# Sch_mcu.net
KiCad netlist of a schematic drawn in Altium Designer
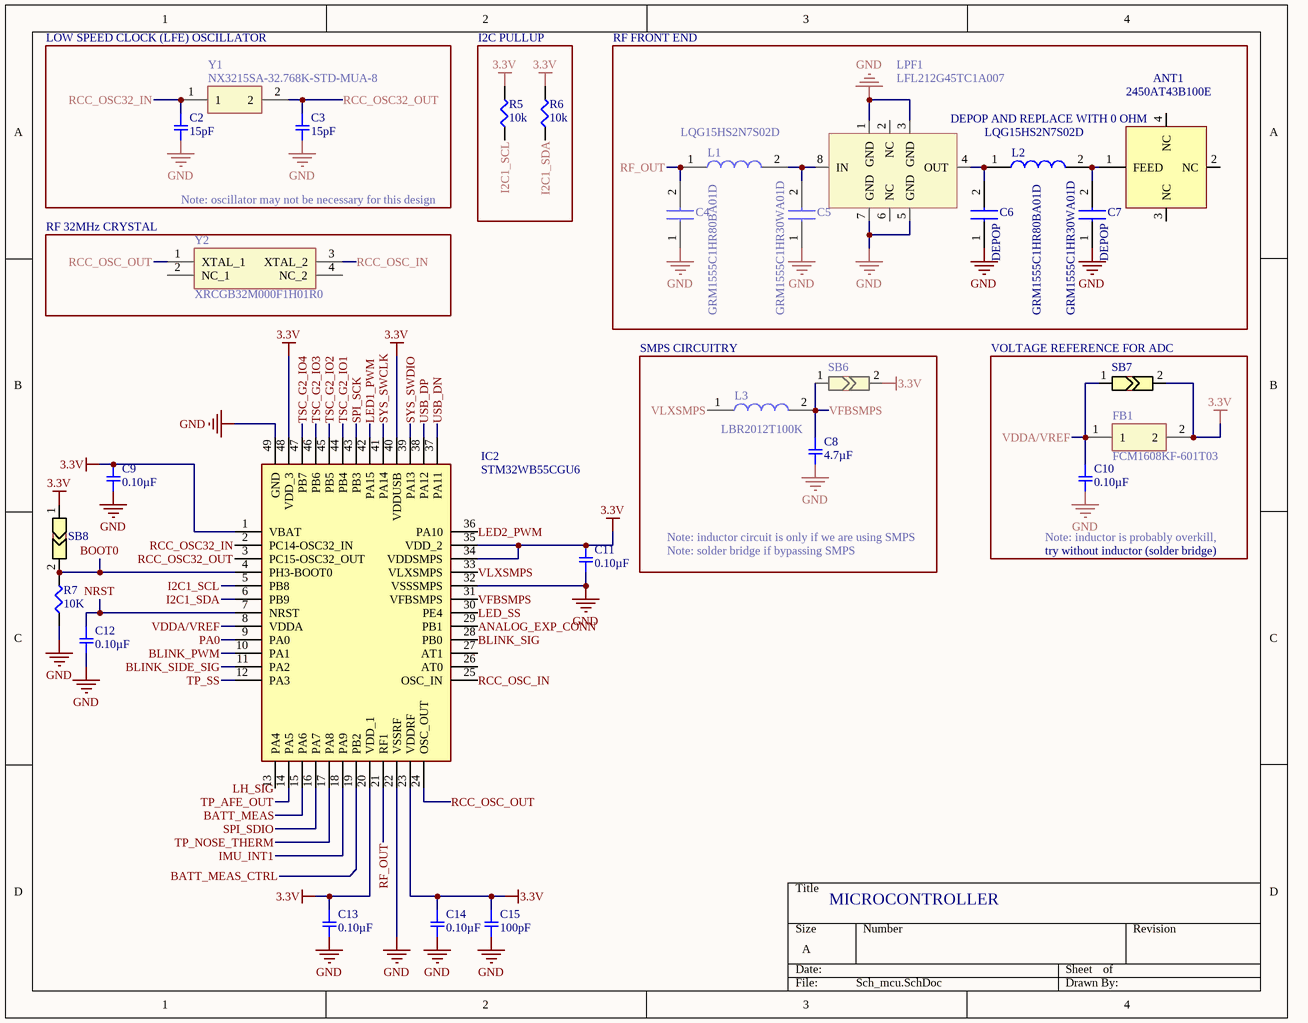
[diagram p0: Sch_mcu.SchDoc]

(export (version "E")
  (design (tool "Eeschema 10.0.6"))
  (components
    (comp (ref "ANT1")
      (value "2450AT43B100E")
      (footprint "2450AT43B100E")
      (libsource (lib "schematic_components") (part "2450AT43B100E"))
    )
    (comp (ref "C2")
      (value "15pF")
      (footprint "SMD-0402C")
      (description "CAP CER 15PF 50V NP0 0402")
      (fields
        (field (name "DIGI-KEY PART NUMBER") "490-11147-1-ND")
        (field (name "PART NUMBER") "GCM1555C1H150JA16D")
      )
      (libsource (lib "capacitor_murata_0402") (part "GCM1555C1H150JA16D"))
    )
    (comp (ref "C3")
      (value "15pF")
      (footprint "SMD-0402C")
      (description "CAP CER 15PF 50V NP0 0402")
      (fields
        (field (name "DIGI-KEY PART NUMBER") "490-11147-1-ND")
        (field (name "PART NUMBER") "GCM1555C1H150JA16D")
      )
      (libsource (lib "capacitor_murata_0402") (part "GCM1555C1H150JA16D"))
    )
    (comp (ref "C4")
      (value "GRM1555C1HR80BA01D")
      (footprint "SamacSys:CAPC1005X55N")
      (description "Capacitor")
      (fields
        (field (name "MOUSER PART NUMBER") "81-GRM1555C1HR80BA1D")
        (field (name "RS PART NUMBER") "8145426P")
      )
      (libsource (lib "*") (part "GRM1555C1HR80BA01D"))
    )
    (comp (ref "C5")
      (value "GRM1555C1HR30WA01D")
      (footprint "SamacSys:CAPC1005X55N")
      (description "Capacitor")
      (fields
        (field (name "MOUSER PART NUMBER") "81-GRM1555C1HR30WA1D")
        (field (name "RS PART NUMBER") "8145394P")
      )
      (libsource (lib "*") (part "GRM1555C1HR30WA01D"))
    )
    (comp (ref "C6")
      (value "GRM1555C1HR80BA01D")
      (footprint "SamacSys:CAPC1005X55N")
      (description "Capacitor")
      (fields
        (field (name "MOUSER PART NUMBER") "81-GRM1555C1HR80BA1D")
        (field (name "RS PART NUMBER") "8145426P")
      )
      (libsource (lib "*") (part "GRM1555C1HR80BA01D"))
    )
    (comp (ref "C7")
      (value "GRM1555C1HR30WA01D")
      (footprint "SamacSys:CAPC1005X55N")
      (description "Capacitor")
      (fields
        (field (name "MOUSER PART NUMBER") "81-GRM1555C1HR30WA1D")
        (field (name "RS PART NUMBER") "8145394P")
      )
      (libsource (lib "*") (part "GRM1555C1HR30WA01D"))
    )
    (comp (ref "C8")
      (value "4.7µF")
      (footprint "SMD-0402C")
      (description "CAP CER 4.7UF 4V X5R 0402")
      (fields
        (field (name "DIGI-KEY PART NUMBER") "490-13231-1-ND")
        (field (name "PART NUMBER") "GRM153R60G475ME15D")
      )
      (libsource (lib "capacitor_murata_0402") (part "GRM153R60G475ME15D"))
    )
    (comp (ref "C9")
      (value "0.10µF")
      (footprint "SMD-0402C")
      (description "CAP CER 0.1UF 16V X7R 0402")
      (fields
        (field (name "DIGI-KEY PART NUMBER") "490-4759-1-ND")
        (field (name "PART NUMBER") "GCM155R71C104KA55D")
      )
      (libsource (lib "capacitor_murata_0402") (part "GCM155R71C104KA55D"))
    )
    (comp (ref "C10")
      (value "0.10µF")
      (footprint "SMD-0402C")
      (description "CAP CER 0.1UF 16V X7R 0402")
      (fields
        (field (name "DIGI-KEY PART NUMBER") "490-4759-1-ND")
        (field (name "PART NUMBER") "GCM155R71C104KA55D")
      )
      (libsource (lib "capacitor_murata_0402") (part "GCM155R71C104KA55D"))
    )
    (comp (ref "C11")
      (value "0.10µF")
      (footprint "SMD-0402C")
      (description "CAP CER 0.1UF 16V X7R 0402")
      (fields
        (field (name "DIGI-KEY PART NUMBER") "490-4759-1-ND")
        (field (name "PART NUMBER") "GCM155R71C104KA55D")
      )
      (libsource (lib "capacitor_murata_0402") (part "GCM155R71C104KA55D"))
    )
    (comp (ref "C12")
      (value "0.10µF")
      (footprint "SMD-0402C")
      (description "CAP CER 0.1UF 16V X7R 0402")
      (fields
        (field (name "DIGI-KEY PART NUMBER") "490-4759-1-ND")
        (field (name "PART NUMBER") "GCM155R71C104KA55D")
      )
      (libsource (lib "capacitor_murata_0402") (part "GCM155R71C104KA55D"))
    )
    (comp (ref "C13")
      (value "0.10µF")
      (footprint "SMD-0402C")
      (description "CAP CER 0.1UF 16V X7R 0402")
      (fields
        (field (name "DIGI-KEY PART NUMBER") "490-4759-1-ND")
        (field (name "PART NUMBER") "GCM155R71C104KA55D")
      )
      (libsource (lib "capacitor_murata_0402") (part "GCM155R71C104KA55D"))
    )
    (comp (ref "C14")
      (value "0.10µF")
      (footprint "SMD-0402C")
      (description "CAP CER 0.1UF 16V X7R 0402")
      (fields
        (field (name "DIGI-KEY PART NUMBER") "490-4759-1-ND")
        (field (name "PART NUMBER") "GCM155R71C104KA55D")
      )
      (libsource (lib "capacitor_murata_0402") (part "GCM155R71C104KA55D"))
    )
    (comp (ref "C15")
      (value "100pF")
      (footprint "SMD-0402C")
      (description "CAP CER 100PF 50V NP0 0402")
      (fields
        (field (name "DIGI-KEY PART NUMBER") "490-10669-1-ND")
        (field (name "PART NUMBER") "GCM1555C1H101JA16D")
      )
      (libsource (lib "capacitor_murata_0402") (part "GCM1555C1H101JA16D"))
    )
    (comp (ref "FB1")
      (value "FCM1608KF-601T03")
      (footprint "SamacSys:BEADC1608X95N")
      (description "Ferrite Bead")
      (libsource (lib "*") (part "FCM1608KF-601T03"))
    )
    (comp (ref "IC2")
      (value "STM32WB55CGU6")
      (footprint "SamacSys:QFN50P700X700X65-49N-D")
      (description "Integrated Circuit")
      (fields (field (name "MOUSER PART NUMBER") "511-STM32WB55CGU6"))
      (libsource (lib "*") (part "STM32WB55CGU6"))
    )
    (comp (ref "L1")
      (value "LQG15HS2N7S02D")
      (footprint "SamacSys:INDC1005X55N")
      (description "Inductor")
      (libsource (lib "*") (part "LQG15HS2N7S02D"))
    )
    (comp (ref "L2")
      (value "LQG15HS2N7S02D")
      (footprint "SamacSys:INDC1005X55N")
      (description "Inductor")
      (libsource (lib "*") (part "LQG15HS2N7S02D"))
    )
    (comp (ref "L3")
      (value "LBR2012T100K")
      (footprint "SamacSys:INDC2012X145N")
      (description "Inductor")
      (fields (field (name "MOUSER PART NUMBER") "963-LBR2012T100K"))
      (libsource (lib "*") (part "LBR2012T100K"))
    )
    (comp (ref "LPF1")
      (value "LFL212G45TC1A007")
      (footprint "custom_footprints:LFL212G45TC1A007")
      (libsource (lib "SamacSys") (part "LFL212G45TC1A007"))
    )
    (comp (ref "R5")
      (value "10k")
      (footprint "SMD-0402-RES")
      (description "RES SMD 10K OHM 5% 1/10W 0402")
      (fields (field (name "PART NUMBER") "ERJ-2GEJ103X") (field (name "DIGI-KEY PART NUMBER") "P10KJCT-ND"))
      (libsource (lib "Panasonic_ERJ_0402") (part "ERJ-2GEJ103X"))
    )
    (comp (ref "R6")
      (value "10k")
      (footprint "SMD-0402-RES")
      (description "RES SMD 10K OHM 5% 1/10W 0402")
      (fields (field (name "PART NUMBER") "ERJ-2GEJ103X") (field (name "DIGI-KEY PART NUMBER") "P10KJCT-ND"))
      (libsource (lib "Panasonic_ERJ_0402") (part "ERJ-2GEJ103X"))
    )
    (comp (ref "R7")
      (value "10K")
      (footprint "SMD-0402-RES")
      (description "RES SMD 10K OHM 1% 1/10W 0402")
      (fields
        (field (name "PART NUMBER") "ERJ-2RKF1003X")
        (field (name "DIGI-KEY PART NUMBER") "P100KLCT-ND")
      )
      (libsource (lib "Panasonic_ERJ_0402") (part "ERJ-2RKF1003X"))
    )
    (comp (ref "SB6")
      (value "SOLDER_JUMPER")
      (footprint "custom_footprints:JUMPER_SMD")
      (libsource (lib "SamacSys") (part "SOLDER_JUMPER"))
    )
    (comp (ref "SB7")
      (value "SOLDER_JUMPER")
      (footprint "custom_footprints:JUMPER_SMD")
      (libsource (lib "SamacSys") (part "SOLDER_JUMPER"))
    )
    (comp (ref "SB8")
      (value "SOLDER_JUMPER")
      (footprint "custom_footprints:JUMPER_SMD")
      (libsource (lib "") (part "SOLDER_JUMPER_1"))
    )
    (comp (ref "Y1")
      (value "NX3215SA-32.768K-STD-MUA-8")
      (footprint "SamacSys:NX3215SA")
      (description "Crystal or Oscillator")
      (fields (field (name "MOUSER PART NUMBER") "344-NX3215SA32768K8"))
      (libsource (lib "*") (part "NX3215SA-32.768K-STD-MUA-8"))
    )
    (comp (ref "Y2")
      (value "XRCGB32M000F1H01R0")
      (footprint "SamacSys:XRCGB32M000F1H01R0")
      (description "Crystal or Oscillator")
      (fields (field (name "MOUSER PART NUMBER") "81-XRCGB32M000F1H01R"))
      (libsource (lib "*") (part "XRCGB32M000F1H01R0"))
    )
  )
  (nets
    (net (code "1") (name "/ANALOG_EXP_CONN") (class "Default")
      (node (ref "IC2") (pin "29") (pinfunction "PB1_29") (pintype "passive"))
    )
    (net (code "2") (name "/BATT_MEAS") (class "Default")
      (node (ref "IC2") (pin "15") (pinfunction "PA6_15") (pintype "passive"))
    )
    (net (code "3") (name "/BATT_MEAS_CTRL") (class "Default")
      (node (ref "IC2") (pin "19") (pinfunction "PB2_19") (pintype "passive"))
    )
    (net (code "4") (name "/BLINK_PWM") (class "Default")
      (node (ref "IC2") (pin "10") (pinfunction "PA1_10") (pintype "passive"))
    )
    (net (code "5") (name "/BLINK_SIDE_SIG") (class "Default")
      (node (ref "IC2") (pin "11") (pinfunction "PA2_11") (pintype "passive"))
    )
    (net (code "6") (name "/BLINK_SIG") (class "Default")
      (node (ref "IC2") (pin "28") (pinfunction "PB0_28") (pintype "passive"))
    )
    (net (code "7") (name "/BOOT0") (class "Default")
      (node (ref "IC2") (pin "4") (pinfunction "PH3-BOOT0_4") (pintype "passive"))
      (node (ref "R7") (pin "2") (pinfunction "2_2") (pintype "passive"))
      (node (ref "SB8") (pin "2") (pinfunction "1_2") (pintype "passive"))
    )
    (net (code "8") (name "/I2C1_SCL") (class "Default")
      (node (ref "IC2") (pin "5") (pinfunction "PB8_5") (pintype "passive"))
      (node (ref "R5") (pin "1") (pinfunction "1_1") (pintype "passive"))
    )
    (net (code "9") (name "/I2C1_SDA") (class "Default")
      (node (ref "IC2") (pin "6") (pinfunction "PB9_6") (pintype "passive"))
      (node (ref "R6") (pin "1") (pinfunction "1_1") (pintype "passive"))
    )
    (net (code "10") (name "/IMU_INT1") (class "Default")
      (node (ref "IC2") (pin "18") (pinfunction "PA9_18") (pintype "passive"))
    )
    (net (code "11") (name "/LED1_PWM") (class "Default")
      (node (ref "IC2") (pin "42") (pinfunction "PA15_42") (pintype "passive"))
    )
    (net (code "12") (name "/LED2_PWM") (class "Default")
      (node (ref "IC2") (pin "36") (pinfunction "PA10_36") (pintype "passive"))
    )
    (net (code "13") (name "/LED_SS") (class "Default")
      (node (ref "IC2") (pin "30") (pinfunction "PE4_30") (pintype "passive"))
    )
    (net (code "14") (name "/LH_SIG") (class "Default")
      (node (ref "IC2") (pin "13") (pinfunction "PA4_13") (pintype "passive"))
    )
    (net (code "15") (name "/NRST") (class "Default")
      (node (ref "C12") (pin "1") (pinfunction "1_1") (pintype "passive"))
      (node (ref "IC2") (pin "7") (pinfunction "NRST_7") (pintype "passive"))
    )
    (net (code "16") (name "/PA0") (class "Default")
      (node (ref "IC2") (pin "9") (pinfunction "PA0_9") (pintype "passive"))
    )
    (net (code "17") (name "/RCC_OSC32_IN") (class "Default")
      (node (ref "C2") (pin "1") (pinfunction "1_1") (pintype "passive"))
      (node (ref "IC2") (pin "2") (pinfunction "PC14-OSC32_IN_2") (pintype "passive"))
      (node (ref "Y1") (pin "1") (pinfunction "1_1") (pintype "passive"))
    )
    (net (code "18") (name "/RCC_OSC32_OUT") (class "Default")
      (node (ref "C3") (pin "1") (pinfunction "1_1") (pintype "passive"))
      (node (ref "IC2") (pin "3") (pinfunction "PC15-OSC32_OUT_3") (pintype "passive"))
      (node (ref "Y1") (pin "2") (pinfunction "2_2") (pintype "passive"))
    )
    (net (code "19") (name "/RCC_OSC_IN") (class "Default")
      (node (ref "IC2") (pin "25") (pinfunction "OSC_IN_25") (pintype "passive"))
      (node (ref "Y2") (pin "3") (pinfunction "XTAL_2_3") (pintype "passive"))
    )
    (net (code "20") (name "/RCC_OSC_OUT") (class "Default")
      (node (ref "IC2") (pin "24") (pinfunction "OSC_OUT_24") (pintype "passive"))
      (node (ref "Y2") (pin "1") (pinfunction "XTAL_1_1") (pintype "passive"))
    )
    (net (code "21") (name "/RF_OUT") (class "Default")
      (node (ref "C4") (pin "2") (pinfunction "2_2") (pintype "passive"))
      (node (ref "IC2") (pin "21") (pinfunction "RF1_21") (pintype "passive"))
      (node (ref "L1") (pin "1") (pinfunction "1_1") (pintype "passive"))
    )
    (net (code "22") (name "/SPI_SCK") (class "Default")
      (node (ref "IC2") (pin "43") (pinfunction "PB3_43") (pintype "passive"))
    )
    (net (code "23") (name "/SPI_SDIO") (class "Default")
      (node (ref "IC2") (pin "16") (pinfunction "PA7_16") (pintype "passive"))
    )
    (net (code "24") (name "/SYS_SWCLK") (class "Default")
      (node (ref "IC2") (pin "41") (pinfunction "PA14_41") (pintype "passive"))
    )
    (net (code "25") (name "/SYS_SWDIO") (class "Default")
      (node (ref "IC2") (pin "39") (pinfunction "PA13_39") (pintype "passive"))
    )
    (net (code "26") (name "/TP_AFE_OUT") (class "Default")
      (node (ref "IC2") (pin "14") (pinfunction "PA5_14") (pintype "passive"))
    )
    (net (code "27") (name "/TP_NOSE_THERM") (class "Default")
      (node (ref "IC2") (pin "17") (pinfunction "PA8_17") (pintype "passive"))
    )
    (net (code "28") (name "/TP_SS") (class "Default")
      (node (ref "IC2") (pin "12") (pinfunction "PA3_12") (pintype "passive"))
    )
    (net (code "29") (name "/TSC_G2_IO1") (class "Default")
      (node (ref "IC2") (pin "44") (pinfunction "PB4_44") (pintype "passive"))
    )
    (net (code "30") (name "/TSC_G2_IO2") (class "Default")
      (node (ref "IC2") (pin "45") (pinfunction "PB5_45") (pintype "passive"))
    )
    (net (code "31") (name "/TSC_G2_IO3") (class "Default")
      (node (ref "IC2") (pin "46") (pinfunction "PB6_46") (pintype "passive"))
    )
    (net (code "32") (name "/TSC_G2_IO4") (class "Default")
      (node (ref "IC2") (pin "47") (pinfunction "PB7_47") (pintype "passive"))
    )
    (net (code "33") (name "/USB_DN") (class "Default")
      (node (ref "IC2") (pin "37") (pinfunction "PA11_37") (pintype "passive"))
    )
    (net (code "34") (name "/USB_DP") (class "Default")
      (node (ref "IC2") (pin "38") (pinfunction "PA12_38") (pintype "passive"))
    )
    (net (code "35") (name "/VDDA{slash}VREF") (class "Default")
      (node (ref "C10") (pin "1") (pinfunction "1_1") (pintype "passive"))
      (node (ref "FB1") (pin "1") (pinfunction "1_1") (pintype "passive"))
      (node (ref "IC2") (pin "8") (pinfunction "VDDA_8") (pintype "passive"))
      (node (ref "SB7") (pin "1") (pinfunction "1_1") (pintype "passive"))
    )
    (net (code "36") (name "/VFBSMPS") (class "Default")
      (node (ref "C8") (pin "1") (pinfunction "1_1") (pintype "passive"))
      (node (ref "IC2") (pin "31") (pinfunction "VFBSMPS_31") (pintype "passive"))
      (node (ref "L3") (pin "2") (pinfunction "2_2") (pintype "passive"))
      (node (ref "SB6") (pin "1") (pinfunction "1_1") (pintype "passive"))
    )
    (net (code "37") (name "/VLXSMPS") (class "Default")
      (node (ref "IC2") (pin "33") (pinfunction "VLXSMPS_33") (pintype "passive"))
      (node (ref "L3") (pin "1") (pinfunction "1_1") (pintype "passive"))
    )
    (net (code "38") (name "3.3V") (class "Default")
      (node (ref "C11") (pin "1") (pinfunction "1_1") (pintype "passive"))
      (node (ref "C13") (pin "1") (pinfunction "1_1") (pintype "passive"))
      (node (ref "C14") (pin "1") (pinfunction "1_1") (pintype "passive"))
      (node (ref "C15") (pin "1") (pinfunction "1_1") (pintype "passive"))
      (node (ref "C9") (pin "1") (pinfunction "1_1") (pintype "passive"))
      (node (ref "FB1") (pin "2") (pinfunction "2_2") (pintype "passive"))
      (node (ref "IC2") (pin "1") (pinfunction "VBAT_1") (pintype "passive"))
      (node (ref "IC2") (pin "20") (pinfunction "VDD_1_20") (pintype "passive"))
      (node (ref "IC2") (pin "23") (pinfunction "VDDRF_23") (pintype "passive"))
      (node (ref "IC2") (pin "34") (pinfunction "VDDSMPS_34") (pintype "passive"))
      (node (ref "IC2") (pin "35") (pinfunction "VDD_2_35") (pintype "passive"))
      (node (ref "IC2") (pin "40") (pinfunction "VDDUSB_40") (pintype "passive"))
      (node (ref "IC2") (pin "48") (pinfunction "VDD_3_48") (pintype "passive"))
      (node (ref "R5") (pin "2") (pinfunction "2_2") (pintype "passive"))
      (node (ref "R6") (pin "2") (pinfunction "2_2") (pintype "passive"))
      (node (ref "SB6") (pin "2") (pinfunction "1_2") (pintype "passive"))
      (node (ref "SB7") (pin "2") (pinfunction "1_2") (pintype "passive"))
      (node (ref "SB8") (pin "1") (pinfunction "1_1") (pintype "passive"))
    )
    (net (code "39") (name "GND") (class "Default")
      (node (ref "C10") (pin "2") (pinfunction "2_2") (pintype "passive"))
      (node (ref "C11") (pin "2") (pinfunction "2_2") (pintype "passive"))
      (node (ref "C12") (pin "2") (pinfunction "2_2") (pintype "passive"))
      (node (ref "C13") (pin "2") (pinfunction "2_2") (pintype "passive"))
      (node (ref "C14") (pin "2") (pinfunction "2_2") (pintype "passive"))
      (node (ref "C15") (pin "2") (pinfunction "2_2") (pintype "passive"))
      (node (ref "C2") (pin "2") (pinfunction "2_2") (pintype "passive"))
      (node (ref "C3") (pin "2") (pinfunction "2_2") (pintype "passive"))
      (node (ref "C4") (pin "1") (pinfunction "1_1") (pintype "passive"))
      (node (ref "C5") (pin "1") (pinfunction "1_1") (pintype "passive"))
      (node (ref "C6") (pin "1") (pinfunction "1_1") (pintype "passive"))
      (node (ref "C7") (pin "1") (pinfunction "1_1") (pintype "passive"))
      (node (ref "C8") (pin "2") (pinfunction "2_2") (pintype "passive"))
      (node (ref "C9") (pin "2") (pinfunction "2_2") (pintype "passive"))
      (node (ref "IC2") (pin "22") (pinfunction "VSSRF_22") (pintype "passive"))
      (node (ref "IC2") (pin "32") (pinfunction "VSSSMPS_32") (pintype "passive"))
      (node (ref "IC2") (pin "49") (pinfunction "GND_49") (pintype "passive"))
      (node (ref "LPF1") (pin "1") (pinfunction "GND_1") (pintype "passive"))
      (node (ref "LPF1") (pin "3") (pinfunction "GND_3") (pintype "passive"))
      (node (ref "LPF1") (pin "5") (pinfunction "GND_5") (pintype "passive"))
      (node (ref "LPF1") (pin "7") (pinfunction "GND_7") (pintype "passive"))
      (node (ref "R7") (pin "1") (pinfunction "1_1") (pintype "passive"))
    )
    (net (code "40") (name "Net-(ANT1-FEED)") (class "Default")
      (node (ref "ANT1") (pin "1") (pinfunction "FEED_1") (pintype "passive"))
      (node (ref "C7") (pin "2") (pinfunction "2_2") (pintype "passive"))
      (node (ref "L2") (pin "2") (pinfunction "2_2") (pintype "passive"))
    )
    (net (code "41") (name "Net-(LPF1-IN)") (class "Default")
      (node (ref "C5") (pin "2") (pinfunction "2_2") (pintype "passive"))
      (node (ref "L1") (pin "2") (pinfunction "2_2") (pintype "passive"))
      (node (ref "LPF1") (pin "8") (pinfunction "IN_8") (pintype "passive"))
    )
    (net (code "42") (name "Net-(LPF1-OUT)") (class "Default")
      (node (ref "C6") (pin "2") (pinfunction "2_2") (pintype "passive"))
      (node (ref "L2") (pin "1") (pinfunction "1_1") (pintype "passive"))
      (node (ref "LPF1") (pin "4") (pinfunction "OUT_4") (pintype "passive"))
    )
    (net (code "43") (name "unconnected-(ANT1-NC-Pad2)") (class "Default")
      (node (ref "ANT1") (pin "2") (pinfunction "NC_2") (pintype "passive"))
    )
    (net (code "44") (name "unconnected-(ANT1-NC-Pad3)") (class "Default")
      (node (ref "ANT1") (pin "3") (pinfunction "NC_3") (pintype "passive"))
    )
    (net (code "45") (name "unconnected-(ANT1-NC-Pad4)") (class "Default")
      (node (ref "ANT1") (pin "4") (pinfunction "NC_4") (pintype "passive"))
    )
    (net (code "46") (name "unconnected-(IC2-AT0-Pad26)") (class "Default")
      (node (ref "IC2") (pin "26") (pinfunction "AT0_26") (pintype "passive"))
    )
    (net (code "47") (name "unconnected-(IC2-AT1-Pad27)") (class "Default")
      (node (ref "IC2") (pin "27") (pinfunction "AT1_27") (pintype "passive"))
    )
    (net (code "48") (name "unconnected-(LPF1-NC-Pad2)") (class "Default")
      (node (ref "LPF1") (pin "2") (pinfunction "NC_2") (pintype "passive"))
    )
    (net (code "49") (name "unconnected-(LPF1-NC-Pad6)") (class "Default")
      (node (ref "LPF1") (pin "6") (pinfunction "NC_6") (pintype "passive"))
    )
    (net (code "50") (name "unconnected-(Y2-NC_1-Pad2)") (class "Default")
      (node (ref "Y2") (pin "2") (pinfunction "NC_1_2") (pintype "passive"))
    )
    (net (code "51") (name "unconnected-(Y2-NC_2-Pad4)") (class "Default")
      (node (ref "Y2") (pin "4") (pinfunction "NC_2_4") (pintype "passive"))
    )
  )
)
